# rev1.net
KiCad netlist of a schematic drawn in EAGLE
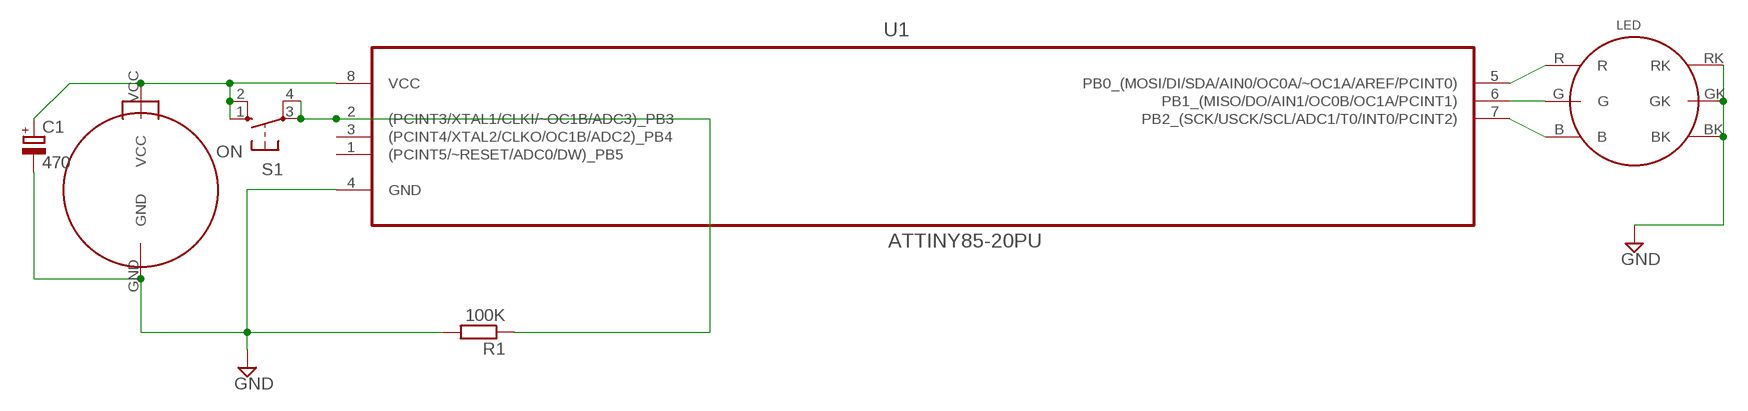
[diagram p0: schematic, sheet 1]

(export (version "E")
  (design (tool "Eeschema 10.0.6"))
  (components
    (comp (ref "C1")
      (value "470")
      (footprint "eagle-import:E5-8,5")
      (libsource (lib "eagle-import") (part "CPOL-EUE5-8.5"))
    )
    (comp (ref "LED")
      (value "3WLED")
      (footprint "eagle-import:3WRGB")
      (libsource (lib "eagle-import") (part "3WLED"))
    )
    (comp (ref "R1")
      (value "100K")
      (footprint "eagle-import:0207_15")
      (libsource (lib "eagle-import") (part "R-EU_0207/15"))
    )
    (comp (ref "S1")
      (value "ON")
      (footprint "eagle-import:B3F-10XX")
      (fields (field (name "MPN") "B3F-1000"))
      (libsource (lib "eagle-import") (part "10-XX"))
    )
    (comp (ref "U$1")
      (value "CR2032_2PIN")
      (footprint "eagle-import:CR2032_2PIN")
      (libsource (lib "eagle-import") (part "CR2032_2PIN"))
    )
    (comp (ref "U1")
      (value "ATTINY85-20PU")
      (footprint "eagle-import:DIP254P762X533-8")
      (libsource (lib "eagle-import") (part "ATTINY85-20PU"))
    )
  )
  (nets
    (net (code "1") (name "GND") (class "Default")
      (node (ref "C1") (pin "-") (pinfunction "-_-") (pintype "passive"))
      (node (ref "LED") (pin "BK") (pinfunction "BK_BK") (pintype "bidirectional"))
      (node (ref "LED") (pin "GK") (pinfunction "GK_GK") (pintype "bidirectional"))
      (node (ref "LED") (pin "RK") (pinfunction "RK_RK") (pintype "bidirectional"))
      (node (ref "R1") (pin "2") (pinfunction "2_2") (pintype "passive"))
      (node (ref "U$1") (pin "GND") (pinfunction "GND_GND") (pintype "bidirectional"))
      (node (ref "U1") (pin "4") (pinfunction "GND_4") (pintype "passive"))
    )
    (net (code "2") (name "Net-(S1-P)") (class "Default")
      (node (ref "R1") (pin "1") (pinfunction "1_1") (pintype "passive"))
      (node (ref "S1") (pin "3") (pinfunction "P_3") (pintype "passive"))
      (node (ref "S1") (pin "4") (pinfunction "P1_4") (pintype "passive"))
      (node (ref "U1") (pin "2") (pinfunction "(PCINT3/XTAL1/CLKI/~{OC1B/ADC3})_PB3_2") (pintype "bidirectional"))
    )
    (net (code "3") (name "Net-(S1-S)") (class "Default")
      (node (ref "C1") (pin "+") (pinfunction "+_+") (pintype "passive"))
      (node (ref "S1") (pin "1") (pinfunction "S_1") (pintype "passive"))
      (node (ref "S1") (pin "2") (pinfunction "S1_2") (pintype "passive"))
      (node (ref "U$1") (pin "VCC") (pinfunction "VCC_VCC") (pintype "bidirectional"))
      (node (ref "U1") (pin "8") (pinfunction "VCC_8") (pintype "power_in"))
    )
    (net (code "4") (name "Net-(U1-PB0_(MOSI{slash}DI{slash}SDA{slash}AIN0{slash}OC0A{slash}~{OC1A{slash}AREF{slash}PCINT0}))") (class "Default")
      (node (ref "LED") (pin "R") (pinfunction "R_R") (pintype "bidirectional"))
      (node (ref "U1") (pin "5") (pinfunction "PB0_(MOSI/DI/SDA/AIN0/OC0A/~{OC1A/AREF/PCINT0})_5") (pintype "bidirectional"))
    )
    (net (code "5") (name "Net-(U1-PB1_(MISO{slash}DO{slash}AIN1{slash}OC0B{slash}OC1A{slash}PCINT1))") (class "Default")
      (node (ref "LED") (pin "G") (pinfunction "G_G") (pintype "bidirectional"))
      (node (ref "U1") (pin "6") (pinfunction "PB1_(MISO/DO/AIN1/OC0B/OC1A/PCINT1)_6") (pintype "bidirectional"))
    )
    (net (code "6") (name "Net-(U1-PB2_(SCK{slash}USCK{slash}SCL{slash}ADC1{slash}T0{slash}INT0{slash}PCINT2))") (class "Default")
      (node (ref "LED") (pin "B") (pinfunction "B_B") (pintype "bidirectional"))
      (node (ref "U1") (pin "7") (pinfunction "PB2_(SCK/USCK/SCL/ADC1/T0/INT0/PCINT2)_7") (pintype "bidirectional"))
    )
    (net (code "7") (name "unconnected-(U1-(PCINT4{slash}XTAL2{slash}CLKO{slash}OC1B{slash}ADC2)_PB4-Pad3)") (class "Default")
      (node (ref "U1") (pin "3") (pinfunction "(PCINT4/XTAL2/CLKO/OC1B/ADC2)_PB4_3") (pintype "bidirectional"))
    )
    (net (code "8") (name "unconnected-(U1-(PCINT5{slash}~{RESET{slash}ADC0{slash}DW})_PB5-Pad1)") (class "Default")
      (node (ref "U1") (pin "1") (pinfunction "(PCINT5/~{RESET/ADC0/DW})_PB5_1") (pintype "bidirectional"))
    )
  )
)
